# PROC054D_System_Power.net
KiCad netlist of a schematic drawn in Altium Designer
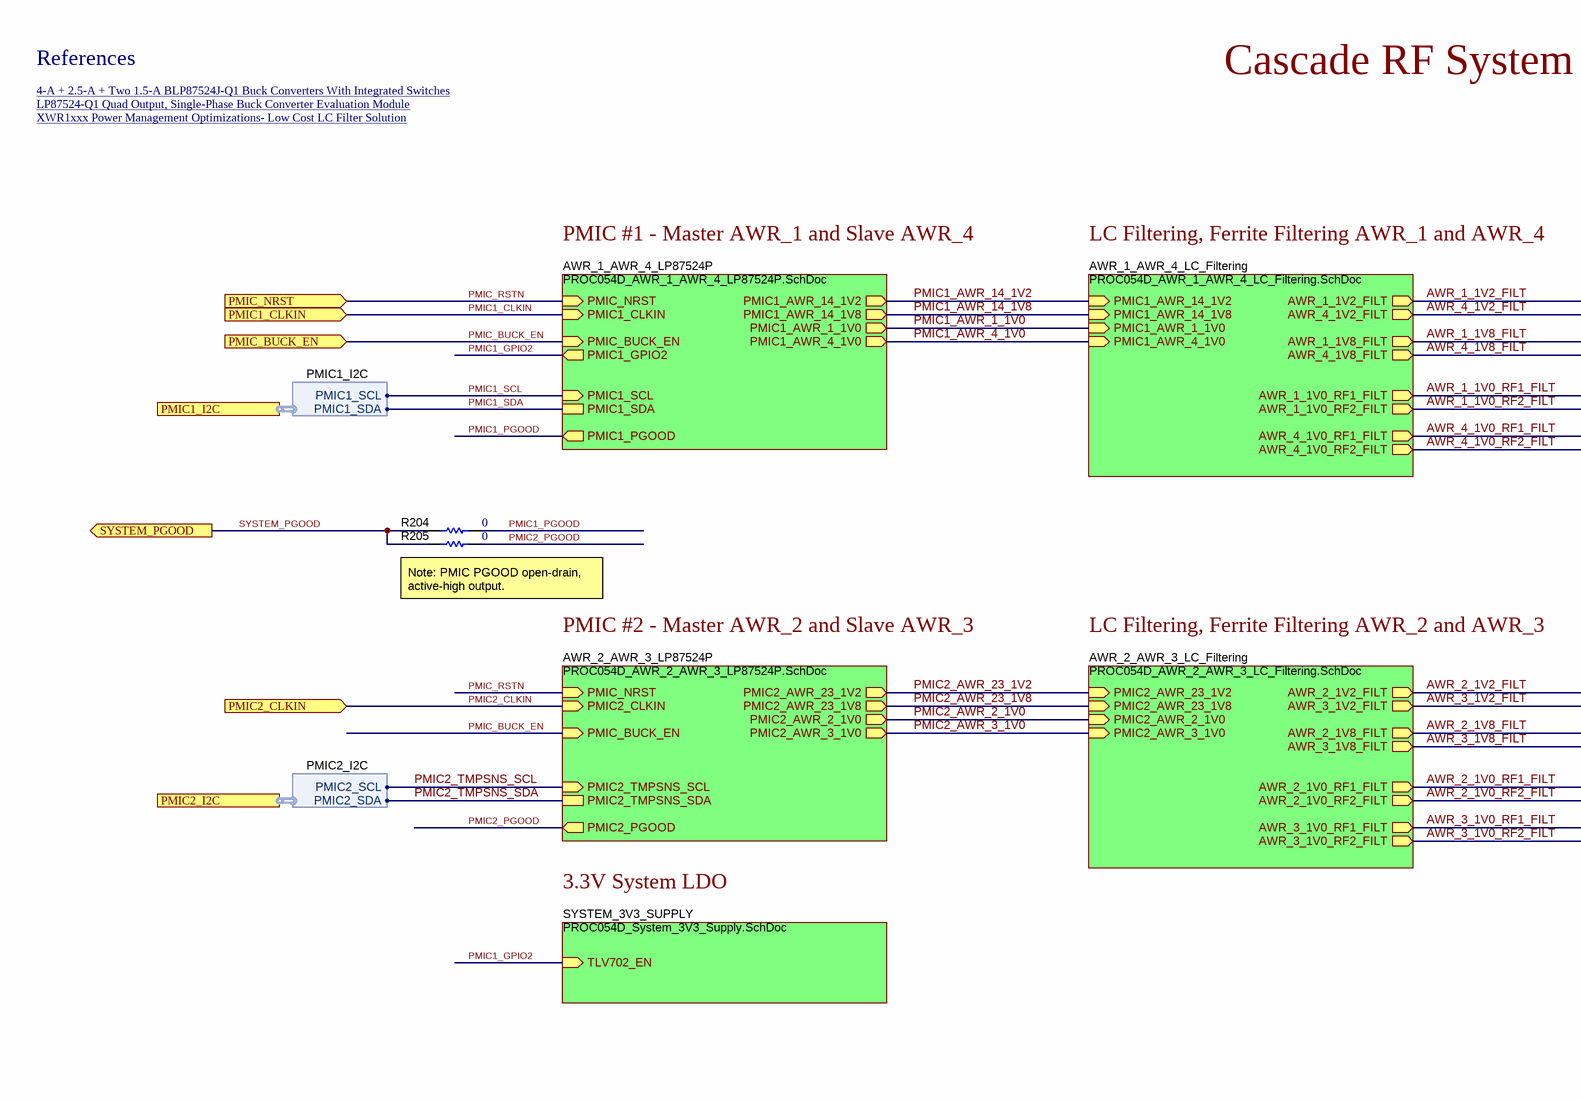
[diagram p0: PROC054D_System_Power.SchDoc, top left]
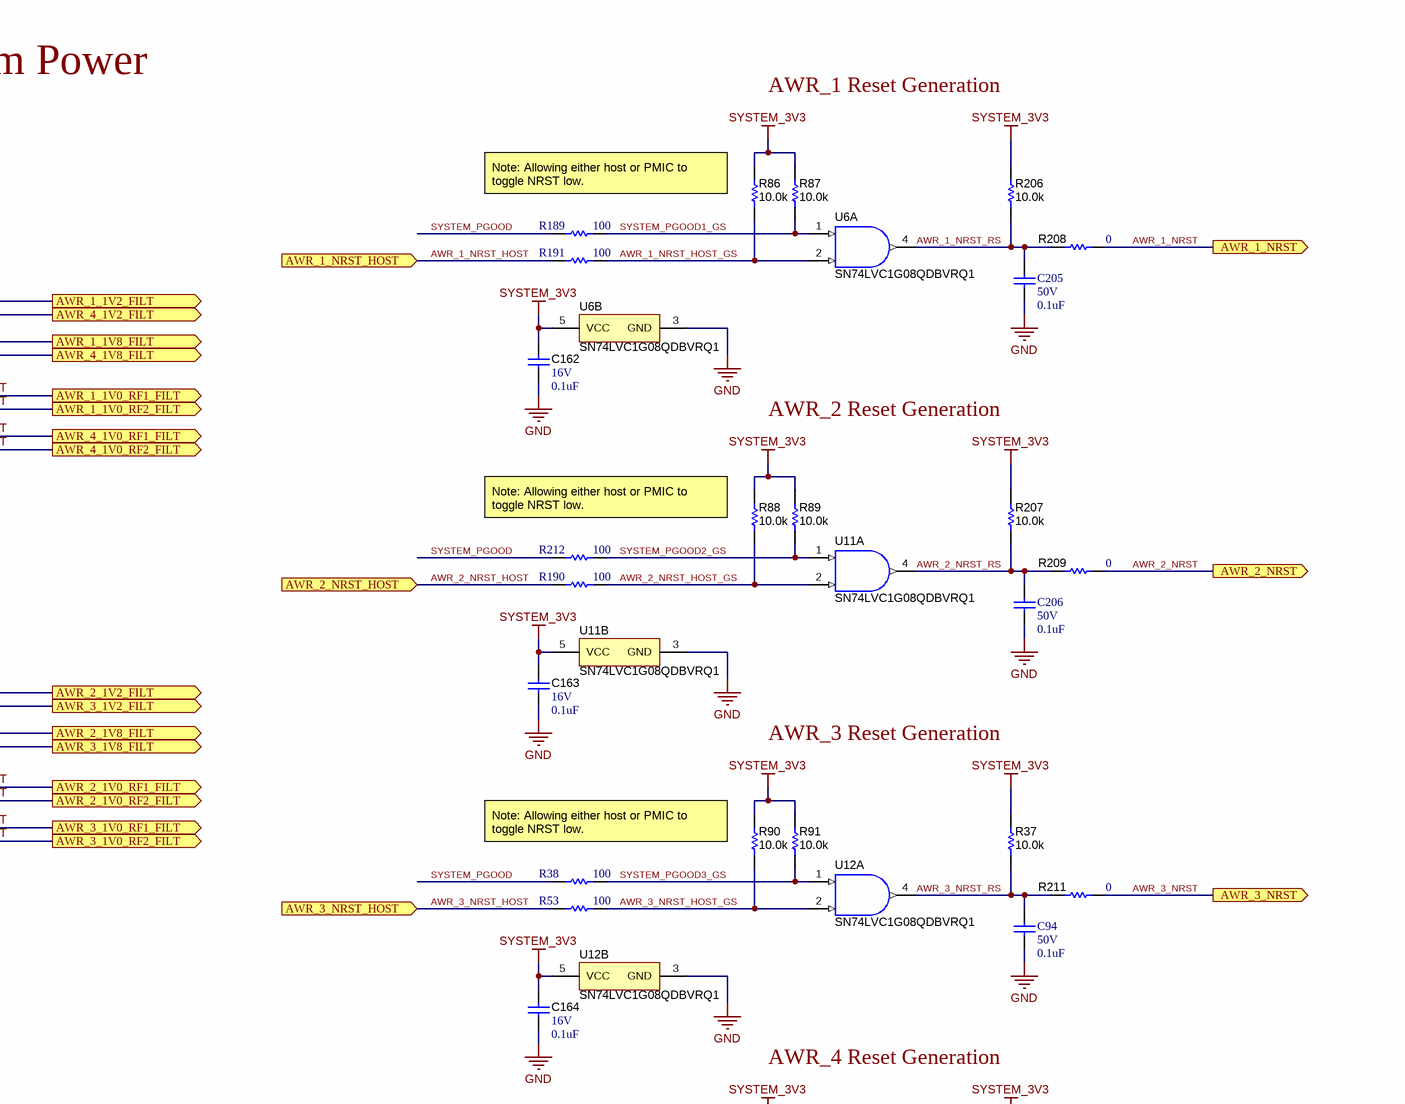
[diagram p1: PROC054D_System_Power.SchDoc, top right]
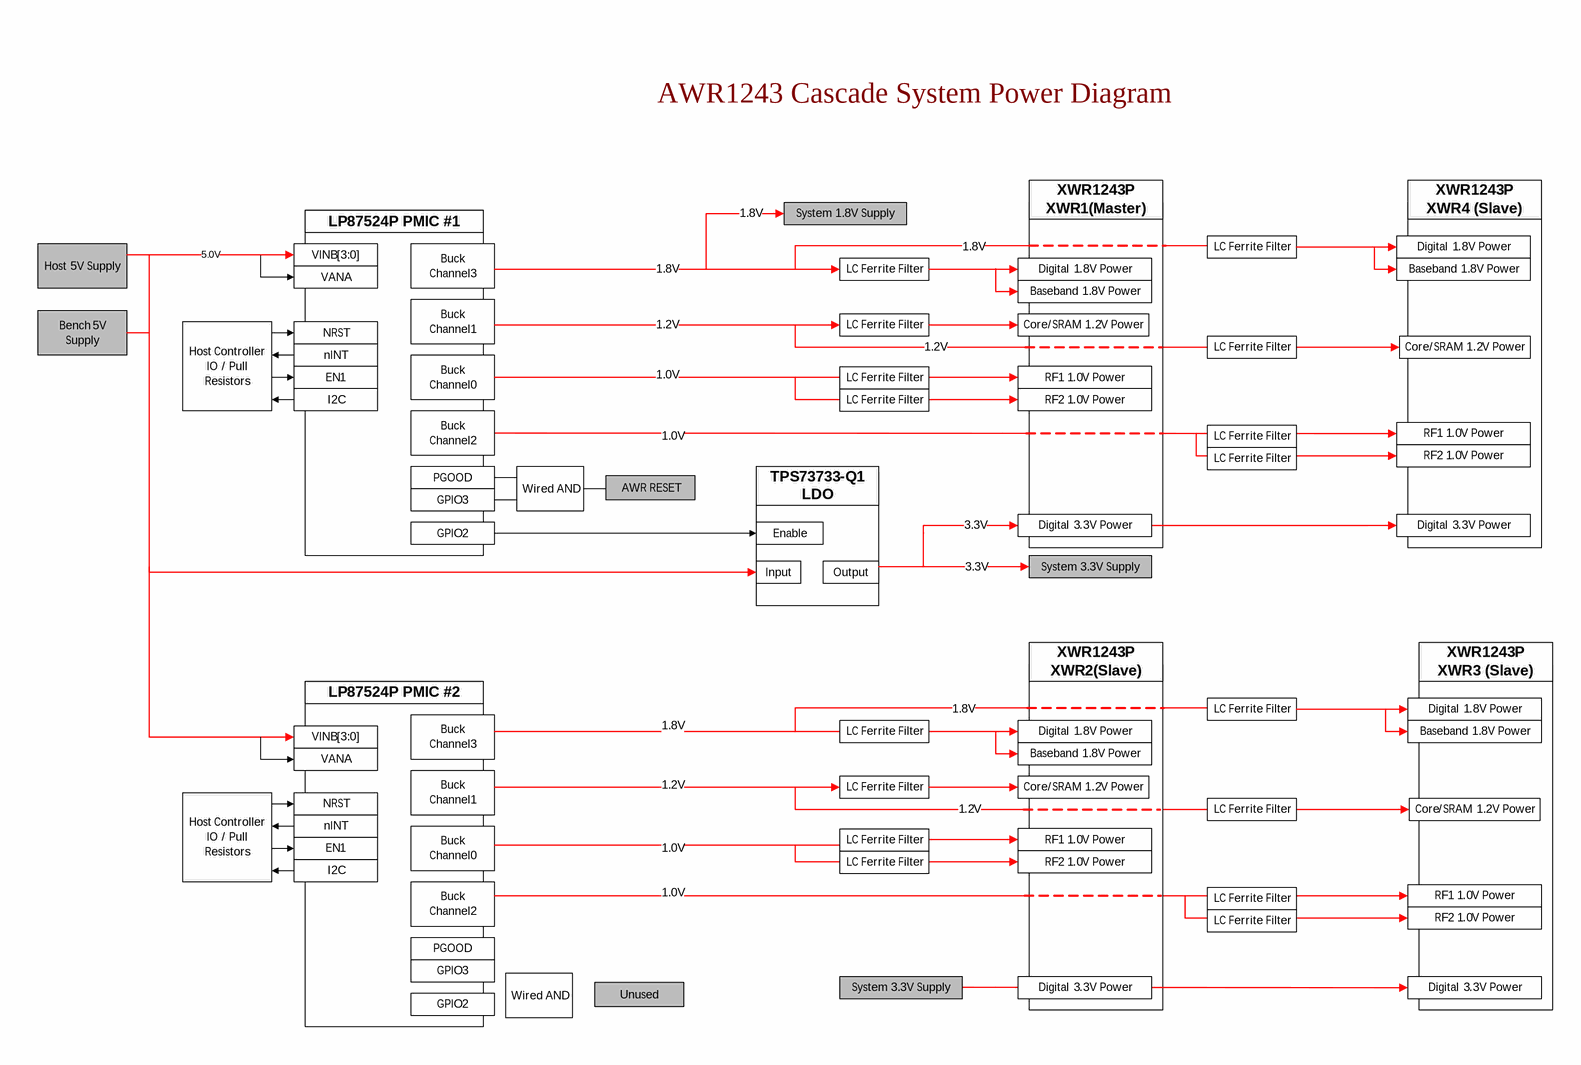
[diagram p2: PROC054D_System_Power.SchDoc, bottom left]
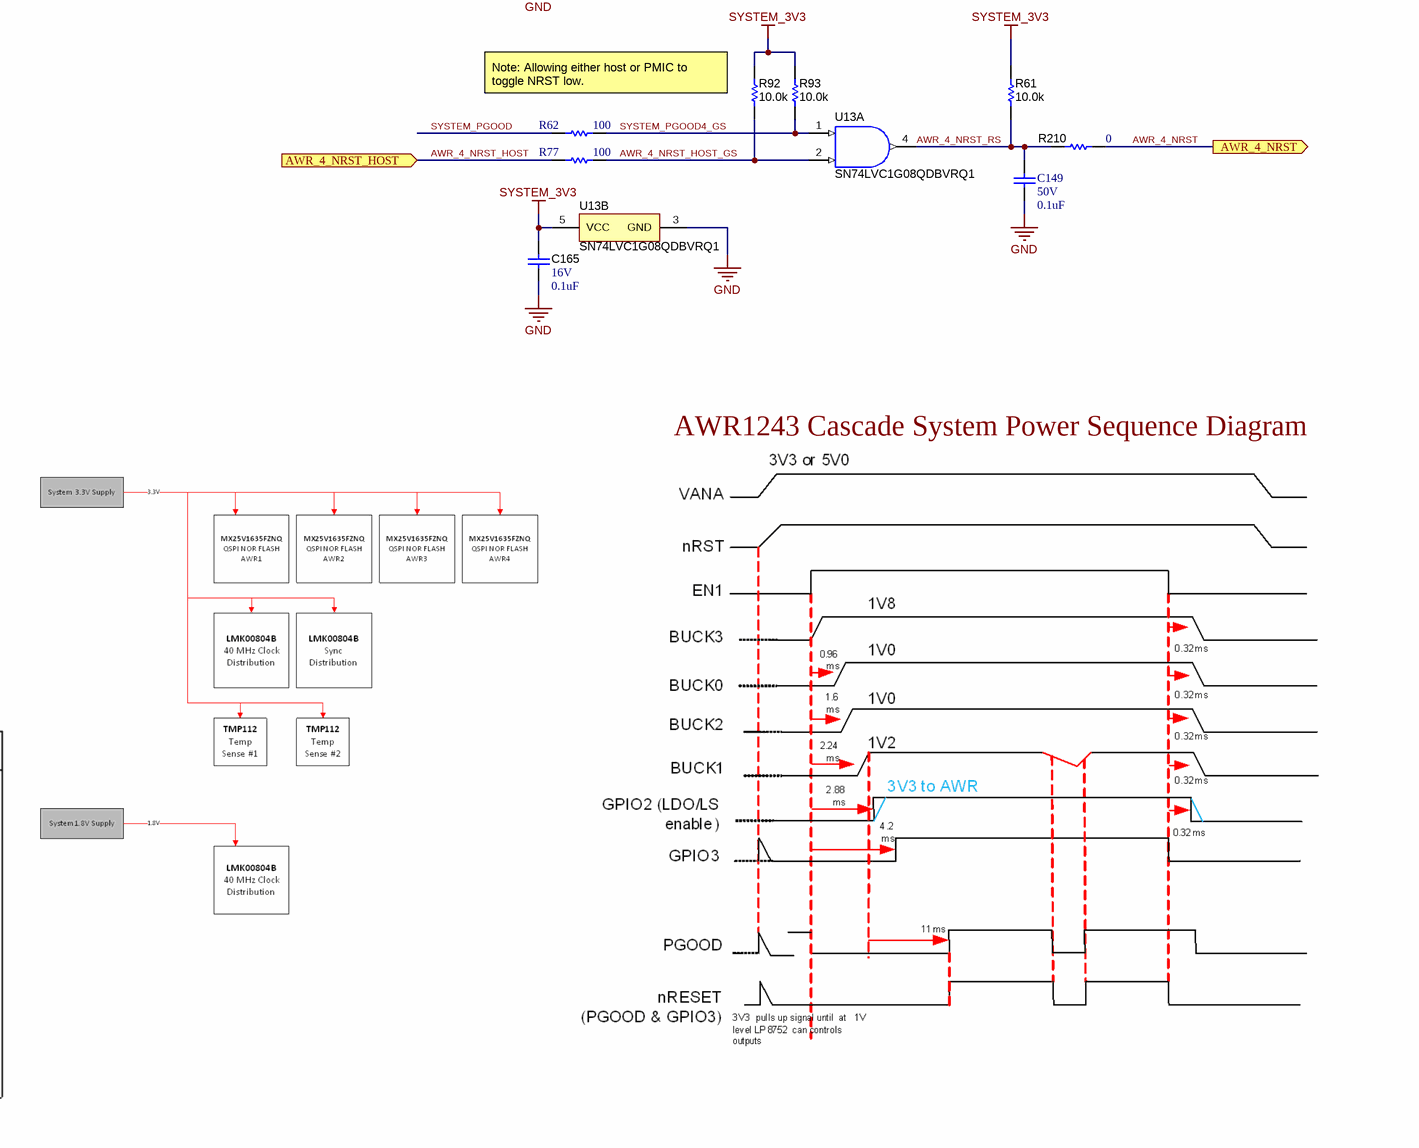
[diagram p3: PROC054D_System_Power.SchDoc, bottom right]

(export (version "E")
  (design (tool "Eeschema 10.0.6"))
  (components
    (comp (ref "C94")
      (value "CGA2B3X7R1H104K050BB")
      (footprint "0402")
      (description "CAP, CERM, 0.1 uF, 50 V, +/- 10%, X7R, AEC-Q200 Grade 1, 0402")
      (fields
        (field (name "MANUFACTURER") "TDK")
        (field (name "VDC_V") "50V")
        (field (name "VALUEDISPLAYED") "0.1uF")
        (field (name "PUBLISHER") "Texas Instruments")
      )
      (libsource (lib "Altium Vault - TI") (part "Capacitor"))
    )
    (comp (ref "C149")
      (value "CGA2B3X7R1H104K050BB")
      (footprint "0402")
      (description "CAP, CERM, 0.1 uF, 50 V, +/- 10%, X7R, AEC-Q200 Grade 1, 0402")
      (fields
        (field (name "MANUFACTURER") "TDK")
        (field (name "VDC_V") "50V")
        (field (name "VALUEDISPLAYED") "0.1uF")
        (field (name "PUBLISHER") "Texas Instruments")
      )
      (libsource (lib "Altium Vault - TI") (part "Capacitor"))
    )
    (comp (ref "C162")
      (value "GCM155R71C104KA55D")
      (footprint "0402")
      (description "CAP, CERM, 0.1 uF, 16 V, +/- 10%, X7R, 0402")
      (fields
        (field (name "MANUFACTURER") "MuRata")
        (field (name "VDC_V") "16V")
        (field (name "VALUEDISPLAYED") "0.1uF")
        (field (name "PUBLISHER") "Texas Instruments")
      )
      (libsource (lib "Altium Vault - TI") (part "Capacitor"))
    )
    (comp (ref "C163")
      (value "GCM155R71C104KA55D")
      (footprint "0402")
      (description "CAP, CERM, 0.1 uF, 16 V, +/- 10%, X7R, 0402")
      (fields
        (field (name "MANUFACTURER") "MuRata")
        (field (name "VDC_V") "16V")
        (field (name "VALUEDISPLAYED") "0.1uF")
        (field (name "PUBLISHER") "Texas Instruments")
      )
      (libsource (lib "Altium Vault - TI") (part "Capacitor"))
    )
    (comp (ref "C164")
      (value "GCM155R71C104KA55D")
      (footprint "0402")
      (description "CAP, CERM, 0.1 uF, 16 V, +/- 10%, X7R, 0402")
      (fields
        (field (name "MANUFACTURER") "MuRata")
        (field (name "VDC_V") "16V")
        (field (name "VALUEDISPLAYED") "0.1uF")
        (field (name "PUBLISHER") "Texas Instruments")
      )
      (libsource (lib "Altium Vault - TI") (part "Capacitor"))
    )
    (comp (ref "C165")
      (value "GCM155R71C104KA55D")
      (footprint "0402")
      (description "CAP, CERM, 0.1 uF, 16 V, +/- 10%, X7R, 0402")
      (fields
        (field (name "MANUFACTURER") "MuRata")
        (field (name "VDC_V") "16V")
        (field (name "VALUEDISPLAYED") "0.1uF")
        (field (name "PUBLISHER") "Texas Instruments")
      )
      (libsource (lib "Altium Vault - TI") (part "Capacitor"))
    )
    (comp (ref "C205")
      (value "CGA2B3X7R1H104K050BB")
      (footprint "0402")
      (description "CAP, CERM, 0.1 uF, 50 V, +/- 10%, X7R, AEC-Q200 Grade 1, 0402")
      (fields
        (field (name "MANUFACTURER") "TDK")
        (field (name "VDC_V") "50V")
        (field (name "VALUEDISPLAYED") "0.1uF")
        (field (name "PUBLISHER") "Texas Instruments")
      )
      (libsource (lib "Altium Vault - TI") (part "Capacitor"))
    )
    (comp (ref "C206")
      (value "CGA2B3X7R1H104K050BB")
      (footprint "0402")
      (description "CAP, CERM, 0.1 uF, 50 V, +/- 10%, X7R, AEC-Q200 Grade 1, 0402")
      (fields
        (field (name "MANUFACTURER") "TDK")
        (field (name "VDC_V") "50V")
        (field (name "VALUEDISPLAYED") "0.1uF")
        (field (name "PUBLISHER") "Texas Instruments")
      )
      (libsource (lib "Altium Vault - TI") (part "Capacitor"))
    )
    (comp (ref "R37")
      (value "CRCW040210K0FKED")
      (footprint "0402")
      (description "RES, 10.0 k, 1%, 0.063 W, AEC-Q200 Grade 0, 0402")
      (fields (field (name "MANUFACTURER") "Vishay-Dale") (field (name "VALUEDISPLAYED") "10.0k"))
      (libsource (lib "Altium Vault - TI") (part "Resistor"))
    )
    (comp (ref "R38")
      (value "MCS0402MD1000BE100")
      (footprint "0402")
      (description "RES, 100, 0.1%, 0.1 W, AEC-Q200 Grade 0, 0402")
      (fields
        (field (name "MANUFACTURER") "Vishay/Beyschlag")
        (field (name "VALUEDISPLAYED") "100")
        (field (name "PUBLISHER") "Texas Instruments")
      )
      (libsource (lib "Altium Vault - TI") (part "Resistor"))
    )
    (comp (ref "R53")
      (value "MCS0402MD1000BE100")
      (footprint "0402")
      (description "RES, 100, 0.1%, 0.1 W, AEC-Q200 Grade 0, 0402")
      (fields
        (field (name "MANUFACTURER") "Vishay/Beyschlag")
        (field (name "VALUEDISPLAYED") "100")
        (field (name "PUBLISHER") "Texas Instruments")
      )
      (libsource (lib "Altium Vault - TI") (part "Resistor"))
    )
    (comp (ref "R61")
      (value "CRCW040210K0FKED")
      (footprint "0402")
      (description "RES, 10.0 k, 1%, 0.063 W, AEC-Q200 Grade 0, 0402")
      (fields (field (name "MANUFACTURER") "Vishay-Dale") (field (name "VALUEDISPLAYED") "10.0k"))
      (libsource (lib "Altium Vault - TI") (part "Resistor"))
    )
    (comp (ref "R62")
      (value "MCS0402MD1000BE100")
      (footprint "0402")
      (description "RES, 100, 0.1%, 0.1 W, AEC-Q200 Grade 0, 0402")
      (fields
        (field (name "MANUFACTURER") "Vishay/Beyschlag")
        (field (name "VALUEDISPLAYED") "100")
        (field (name "PUBLISHER") "Texas Instruments")
      )
      (libsource (lib "Altium Vault - TI") (part "Resistor"))
    )
    (comp (ref "R77")
      (value "MCS0402MD1000BE100")
      (footprint "0402")
      (description "RES, 100, 0.1%, 0.1 W, AEC-Q200 Grade 0, 0402")
      (fields
        (field (name "MANUFACTURER") "Vishay/Beyschlag")
        (field (name "VALUEDISPLAYED") "100")
        (field (name "PUBLISHER") "Texas Instruments")
      )
      (libsource (lib "Altium Vault - TI") (part "Resistor"))
    )
    (comp (ref "R86")
      (value "CRCW040210K0FKED")
      (footprint "0402")
      (description "RES, 10.0 k, 1%, 0.063 W, AEC-Q200 Grade 0, 0402")
      (fields (field (name "MANUFACTURER") "Vishay-Dale") (field (name "VALUEDISPLAYED") "10.0k"))
      (libsource (lib "Altium Vault - TI") (part "Resistor"))
    )
    (comp (ref "R87")
      (value "CRCW040210K0FKED")
      (footprint "0402")
      (description "RES, 10.0 k, 1%, 0.063 W, AEC-Q200 Grade 0, 0402")
      (fields (field (name "MANUFACTURER") "Vishay-Dale") (field (name "VALUEDISPLAYED") "10.0k"))
      (libsource (lib "Altium Vault - TI") (part "Resistor"))
    )
    (comp (ref "R88")
      (value "CRCW040210K0FKED")
      (footprint "0402")
      (description "RES, 10.0 k, 1%, 0.063 W, AEC-Q200 Grade 0, 0402")
      (fields (field (name "MANUFACTURER") "Vishay-Dale") (field (name "VALUEDISPLAYED") "10.0k"))
      (libsource (lib "Altium Vault - TI") (part "Resistor"))
    )
    (comp (ref "R89")
      (value "CRCW040210K0FKED")
      (footprint "0402")
      (description "RES, 10.0 k, 1%, 0.063 W, AEC-Q200 Grade 0, 0402")
      (fields (field (name "MANUFACTURER") "Vishay-Dale") (field (name "VALUEDISPLAYED") "10.0k"))
      (libsource (lib "Altium Vault - TI") (part "Resistor"))
    )
    (comp (ref "R90")
      (value "CRCW040210K0FKED")
      (footprint "0402")
      (description "RES, 10.0 k, 1%, 0.063 W, AEC-Q200 Grade 0, 0402")
      (fields (field (name "MANUFACTURER") "Vishay-Dale") (field (name "VALUEDISPLAYED") "10.0k"))
      (libsource (lib "Altium Vault - TI") (part "Resistor"))
    )
    (comp (ref "R91")
      (value "CRCW040210K0FKED")
      (footprint "0402")
      (description "RES, 10.0 k, 1%, 0.063 W, AEC-Q200 Grade 0, 0402")
      (fields (field (name "MANUFACTURER") "Vishay-Dale") (field (name "VALUEDISPLAYED") "10.0k"))
      (libsource (lib "Altium Vault - TI") (part "Resistor"))
    )
    (comp (ref "R92")
      (value "CRCW040210K0FKED")
      (footprint "0402")
      (description "RES, 10.0 k, 1%, 0.063 W, AEC-Q200 Grade 0, 0402")
      (fields (field (name "MANUFACTURER") "Vishay-Dale") (field (name "VALUEDISPLAYED") "10.0k"))
      (libsource (lib "Altium Vault - TI") (part "Resistor"))
    )
    (comp (ref "R93")
      (value "CRCW040210K0FKED")
      (footprint "0402")
      (description "RES, 10.0 k, 1%, 0.063 W, AEC-Q200 Grade 0, 0402")
      (fields (field (name "MANUFACTURER") "Vishay-Dale") (field (name "VALUEDISPLAYED") "10.0k"))
      (libsource (lib "Altium Vault - TI") (part "Resistor"))
    )
    (comp (ref "R189")
      (value "MCS0402MD1000BE100")
      (footprint "0402")
      (description "RES, 100, 0.1%, 0.1 W, AEC-Q200 Grade 0, 0402")
      (fields
        (field (name "MANUFACTURER") "Vishay/Beyschlag")
        (field (name "VALUEDISPLAYED") "100")
        (field (name "PUBLISHER") "Texas Instruments")
      )
      (libsource (lib "Altium Vault - TI") (part "Resistor"))
    )
    (comp (ref "R190")
      (value "MCS0402MD1000BE100")
      (footprint "0402")
      (description "RES, 100, 0.1%, 0.1 W, AEC-Q200 Grade 0, 0402")
      (fields
        (field (name "MANUFACTURER") "Vishay/Beyschlag")
        (field (name "VALUEDISPLAYED") "100")
        (field (name "PUBLISHER") "Texas Instruments")
      )
      (libsource (lib "Altium Vault - TI") (part "Resistor"))
    )
    (comp (ref "R191")
      (value "MCS0402MD1000BE100")
      (footprint "0402")
      (description "RES, 100, 0.1%, 0.1 W, AEC-Q200 Grade 0, 0402")
      (fields
        (field (name "MANUFACTURER") "Vishay/Beyschlag")
        (field (name "VALUEDISPLAYED") "100")
        (field (name "PUBLISHER") "Texas Instruments")
      )
      (libsource (lib "Altium Vault - TI") (part "Resistor"))
    )
    (comp (ref "R204")
      (value "ERJ-2GE0R00X")
      (footprint "0402")
      (description "RES, 0, 5%, 0.1 W, AEC-Q200 Grade 0, 0402")
      (fields (field (name "MANUFACTURER") "Panasonic") (field (name "VALUEDISPLAYED") "0"))
      (libsource (lib "Altium Vault - TI") (part "Resistor"))
    )
    (comp (ref "R205")
      (value "ERJ-2GE0R00X")
      (footprint "0402")
      (description "RES, 0, 5%, 0.1 W, AEC-Q200 Grade 0, 0402")
      (fields (field (name "MANUFACTURER") "Panasonic") (field (name "VALUEDISPLAYED") "0"))
      (libsource (lib "Altium Vault - TI") (part "Resistor"))
    )
    (comp (ref "R206")
      (value "CRCW040210K0FKED")
      (footprint "0402")
      (description "RES, 10.0 k, 1%, 0.063 W, AEC-Q200 Grade 0, 0402")
      (fields (field (name "MANUFACTURER") "Vishay-Dale") (field (name "VALUEDISPLAYED") "10.0k"))
      (libsource (lib "Altium Vault - TI") (part "Resistor"))
    )
    (comp (ref "R207")
      (value "CRCW040210K0FKED")
      (footprint "0402")
      (description "RES, 10.0 k, 1%, 0.063 W, AEC-Q200 Grade 0, 0402")
      (fields (field (name "MANUFACTURER") "Vishay-Dale") (field (name "VALUEDISPLAYED") "10.0k"))
      (libsource (lib "Altium Vault - TI") (part "Resistor"))
    )
    (comp (ref "R208")
      (value "ERJ-2GE0R00X")
      (footprint "0402")
      (description "RES, 0, 5%, 0.1 W, AEC-Q200 Grade 0, 0402")
      (fields (field (name "MANUFACTURER") "Panasonic") (field (name "VALUEDISPLAYED") "0"))
      (libsource (lib "Altium Vault - TI") (part "Resistor"))
    )
    (comp (ref "R209")
      (value "ERJ-2GE0R00X")
      (footprint "0402")
      (description "RES, 0, 5%, 0.1 W, AEC-Q200 Grade 0, 0402")
      (fields (field (name "MANUFACTURER") "Panasonic") (field (name "VALUEDISPLAYED") "0"))
      (libsource (lib "Altium Vault - TI") (part "Resistor"))
    )
    (comp (ref "R210")
      (value "ERJ-2GE0R00X")
      (footprint "0402")
      (description "RES, 0, 5%, 0.1 W, AEC-Q200 Grade 0, 0402")
      (fields (field (name "MANUFACTURER") "Panasonic") (field (name "VALUEDISPLAYED") "0"))
      (libsource (lib "Altium Vault - TI") (part "Resistor"))
    )
    (comp (ref "R211")
      (value "ERJ-2GE0R00X")
      (footprint "0402")
      (description "RES, 0, 5%, 0.1 W, AEC-Q200 Grade 0, 0402")
      (fields (field (name "MANUFACTURER") "Panasonic") (field (name "VALUEDISPLAYED") "0"))
      (libsource (lib "Altium Vault - TI") (part "Resistor"))
    )
    (comp (ref "R212")
      (value "MCS0402MD1000BE100")
      (footprint "0402")
      (description "RES, 100, 0.1%, 0.1 W, AEC-Q200 Grade 0, 0402")
      (fields
        (field (name "MANUFACTURER") "Vishay/Beyschlag")
        (field (name "VALUEDISPLAYED") "100")
        (field (name "PUBLISHER") "Texas Instruments")
      )
      (libsource (lib "Altium Vault - TI") (part "Resistor"))
    )
    (comp (ref "U6")
      (value "SN74LVC1G08QDBVRQ1")
      (footprint "DBV0005A_N")
      (description "Automotive Catalog Single 2-Input Positive-AND Gate, DBV0005A, LARGE T&R")
      (fields
        (field (name "MANUFACTURER") "Texas Instruments")
        (field (name "GENERIC PART NUMBER") "SN74LVC1G08-Q1")
        (field (name "PARTNUMBER") "SN74LVC1G08QDBVRQ1")
      )
      (libsource (lib "Altium Vault - TI") (part "TI-SN74XXX1X08-5"))
    )
    (comp (ref "U11")
      (value "SN74LVC1G08QDBVRQ1")
      (footprint "DBV0005A_N")
      (description "Automotive Catalog Single 2-Input Positive-AND Gate, DBV0005A, LARGE T&R")
      (fields
        (field (name "MANUFACTURER") "Texas Instruments")
        (field (name "GENERIC PART NUMBER") "SN74LVC1G08-Q1")
        (field (name "PARTNUMBER") "SN74LVC1G08QDBVRQ1")
      )
      (libsource (lib "Altium Vault - TI") (part "TI-SN74XXX1X08-5"))
    )
    (comp (ref "U12")
      (value "SN74LVC1G08QDBVRQ1")
      (footprint "DBV0005A_N")
      (description "Automotive Catalog Single 2-Input Positive-AND Gate, DBV0005A, LARGE T&R")
      (fields
        (field (name "MANUFACTURER") "Texas Instruments")
        (field (name "GENERIC PART NUMBER") "SN74LVC1G08-Q1")
        (field (name "PARTNUMBER") "SN74LVC1G08QDBVRQ1")
      )
      (libsource (lib "Altium Vault - TI") (part "TI-SN74XXX1X08-5"))
    )
    (comp (ref "U13")
      (value "SN74LVC1G08QDBVRQ1")
      (footprint "DBV0005A_N")
      (description "Automotive Catalog Single 2-Input Positive-AND Gate, DBV0005A, LARGE T&R")
      (fields
        (field (name "MANUFACTURER") "Texas Instruments")
        (field (name "GENERIC PART NUMBER") "SN74LVC1G08-Q1")
        (field (name "PARTNUMBER") "SN74LVC1G08QDBVRQ1")
      )
      (libsource (lib "Altium Vault - TI") (part "TI-SN74XXX1X08-5"))
    )
  )
  (nets
    (net (code "7") (name "/AWR_1_NRST") (class "Default")
      (node (ref "R208") (pin "2") (pinfunction "2_2") (pintype "passive"))
    )
    (net (code "8") (name "/AWR_1_NRST_HOST") (class "Default")
      (node (ref "R191") (pin "1") (pinfunction "1_1") (pintype "passive"))
    )
    (net (code "9") (name "/AWR_1_NRST_HOST_GS") (class "Default")
      (node (ref "R191") (pin "2") (pinfunction "2_2") (pintype "passive"))
      (node (ref "R86") (pin "1") (pinfunction "1_1") (pintype "passive"))
      (node (ref "U6") (pin "2") (pinfunction "B_2") (pintype "input"))
    )
    (net (code "10") (name "/AWR_1_NRST_RS") (class "Default")
      (node (ref "C205") (pin "1") (pinfunction "1_1") (pintype "passive"))
      (node (ref "R206") (pin "1") (pinfunction "1_1") (pintype "passive"))
      (node (ref "R208") (pin "1") (pinfunction "1_1") (pintype "passive"))
      (node (ref "U6") (pin "4") (pinfunction "Y_4") (pintype "output"))
    )
    (net (code "15") (name "/AWR_2_NRST") (class "Default")
      (node (ref "R209") (pin "2") (pinfunction "2_2") (pintype "passive"))
    )
    (net (code "16") (name "/AWR_2_NRST_HOST") (class "Default")
      (node (ref "R190") (pin "1") (pinfunction "1_1") (pintype "passive"))
    )
    (net (code "17") (name "/AWR_2_NRST_HOST_GS") (class "Default")
      (node (ref "R190") (pin "2") (pinfunction "2_2") (pintype "passive"))
      (node (ref "R88") (pin "1") (pinfunction "1_1") (pintype "passive"))
      (node (ref "U11") (pin "2") (pinfunction "B_2") (pintype "input"))
    )
    (net (code "18") (name "/AWR_2_NRST_RS") (class "Default")
      (node (ref "C206") (pin "1") (pinfunction "1_1") (pintype "passive"))
      (node (ref "R207") (pin "1") (pinfunction "1_1") (pintype "passive"))
      (node (ref "R209") (pin "1") (pinfunction "1_1") (pintype "passive"))
      (node (ref "U11") (pin "4") (pinfunction "Y_4") (pintype "output"))
    )
    (net (code "23") (name "/AWR_3_NRST") (class "Default")
      (node (ref "R211") (pin "2") (pinfunction "2_2") (pintype "passive"))
    )
    (net (code "24") (name "/AWR_3_NRST_HOST") (class "Default")
      (node (ref "R53") (pin "1") (pinfunction "1_1") (pintype "passive"))
    )
    (net (code "25") (name "/AWR_3_NRST_HOST_GS") (class "Default")
      (node (ref "R53") (pin "2") (pinfunction "2_2") (pintype "passive"))
      (node (ref "R90") (pin "1") (pinfunction "1_1") (pintype "passive"))
      (node (ref "U12") (pin "2") (pinfunction "B_2") (pintype "input"))
    )
    (net (code "26") (name "/AWR_3_NRST_RS") (class "Default")
      (node (ref "C94") (pin "1") (pinfunction "1_1") (pintype "passive"))
      (node (ref "R211") (pin "1") (pinfunction "1_1") (pintype "passive"))
      (node (ref "R37") (pin "1") (pinfunction "1_1") (pintype "passive"))
      (node (ref "U12") (pin "4") (pinfunction "Y_4") (pintype "output"))
    )
    (net (code "31") (name "/AWR_4_NRST") (class "Default")
      (node (ref "R210") (pin "2") (pinfunction "2_2") (pintype "passive"))
    )
    (net (code "32") (name "/AWR_4_NRST_HOST") (class "Default")
      (node (ref "R77") (pin "1") (pinfunction "1_1") (pintype "passive"))
    )
    (net (code "33") (name "/AWR_4_NRST_HOST_GS") (class "Default")
      (node (ref "R77") (pin "2") (pinfunction "2_2") (pintype "passive"))
      (node (ref "R92") (pin "1") (pinfunction "1_1") (pintype "passive"))
      (node (ref "U13") (pin "2") (pinfunction "B_2") (pintype "input"))
    )
    (net (code "34") (name "/AWR_4_NRST_RS") (class "Default")
      (node (ref "C149") (pin "1") (pinfunction "1_1") (pintype "passive"))
      (node (ref "R210") (pin "1") (pinfunction "1_1") (pintype "passive"))
      (node (ref "R61") (pin "1") (pinfunction "1_1") (pintype "passive"))
      (node (ref "U13") (pin "4") (pinfunction "Y_4") (pintype "output"))
    )
    (net (code "41") (name "/PMIC1_PGOOD") (class "Default")
      (node (ref "R204") (pin "2") (pinfunction "2_2") (pintype "passive"))
    )
    (net (code "49") (name "/PMIC2_PGOOD") (class "Default")
      (node (ref "R205") (pin "2") (pinfunction "2_2") (pintype "passive"))
    )
    (net (code "54") (name "/SYSTEM_PGOOD") (class "Default")
      (node (ref "R189") (pin "1") (pinfunction "1_1") (pintype "passive"))
      (node (ref "R204") (pin "1") (pinfunction "1_1") (pintype "passive"))
      (node (ref "R205") (pin "1") (pinfunction "1_1") (pintype "passive"))
      (node (ref "R212") (pin "1") (pinfunction "1_1") (pintype "passive"))
      (node (ref "R38") (pin "1") (pinfunction "1_1") (pintype "passive"))
      (node (ref "R62") (pin "1") (pinfunction "1_1") (pintype "passive"))
    )
    (net (code "55") (name "/SYSTEM_PGOOD1_GS") (class "Default")
      (node (ref "R189") (pin "2") (pinfunction "2_2") (pintype "passive"))
      (node (ref "R87") (pin "1") (pinfunction "1_1") (pintype "passive"))
      (node (ref "U6") (pin "1") (pinfunction "A_1") (pintype "input"))
    )
    (net (code "56") (name "/SYSTEM_PGOOD2_GS") (class "Default")
      (node (ref "R212") (pin "2") (pinfunction "2_2") (pintype "passive"))
      (node (ref "R89") (pin "1") (pinfunction "1_1") (pintype "passive"))
      (node (ref "U11") (pin "1") (pinfunction "A_1") (pintype "input"))
    )
    (net (code "57") (name "/SYSTEM_PGOOD3_GS") (class "Default")
      (node (ref "R38") (pin "2") (pinfunction "2_2") (pintype "passive"))
      (node (ref "R91") (pin "1") (pinfunction "1_1") (pintype "passive"))
      (node (ref "U12") (pin "1") (pinfunction "A_1") (pintype "input"))
    )
    (net (code "58") (name "/SYSTEM_PGOOD4_GS") (class "Default")
      (node (ref "R62") (pin "2") (pinfunction "2_2") (pintype "passive"))
      (node (ref "R93") (pin "1") (pinfunction "1_1") (pintype "passive"))
      (node (ref "U13") (pin "1") (pinfunction "A_1") (pintype "input"))
    )
    (net (code "61") (name "GND") (class "Default")
      (node (ref "C149") (pin "2") (pinfunction "2_2") (pintype "passive"))
      (node (ref "C162") (pin "2") (pinfunction "2_2") (pintype "passive"))
      (node (ref "C163") (pin "2") (pinfunction "2_2") (pintype "passive"))
      (node (ref "C164") (pin "2") (pinfunction "2_2") (pintype "passive"))
      (node (ref "C165") (pin "2") (pinfunction "2_2") (pintype "passive"))
      (node (ref "C205") (pin "2") (pinfunction "2_2") (pintype "passive"))
      (node (ref "C206") (pin "2") (pinfunction "2_2") (pintype "passive"))
      (node (ref "C94") (pin "2") (pinfunction "2_2") (pintype "passive"))
      (node (ref "U11") (pin "3") (pinfunction "GND_3") (pintype "power_in"))
      (node (ref "U12") (pin "3") (pinfunction "GND_3") (pintype "power_in"))
      (node (ref "U13") (pin "3") (pinfunction "GND_3") (pintype "power_in"))
      (node (ref "U6") (pin "3") (pinfunction "GND_3") (pintype "power_in"))
    )
    (net (code "62") (name "SYSTEM_3V3") (class "Default")
      (node (ref "C162") (pin "1") (pinfunction "1_1") (pintype "passive"))
      (node (ref "C163") (pin "1") (pinfunction "1_1") (pintype "passive"))
      (node (ref "C164") (pin "1") (pinfunction "1_1") (pintype "passive"))
      (node (ref "C165") (pin "1") (pinfunction "1_1") (pintype "passive"))
      (node (ref "R206") (pin "2") (pinfunction "2_2") (pintype "passive"))
      (node (ref "R207") (pin "2") (pinfunction "2_2") (pintype "passive"))
      (node (ref "R37") (pin "2") (pinfunction "2_2") (pintype "passive"))
      (node (ref "R61") (pin "2") (pinfunction "2_2") (pintype "passive"))
      (node (ref "R86") (pin "2") (pinfunction "2_2") (pintype "passive"))
      (node (ref "R87") (pin "2") (pinfunction "2_2") (pintype "passive"))
      (node (ref "R88") (pin "2") (pinfunction "2_2") (pintype "passive"))
      (node (ref "R89") (pin "2") (pinfunction "2_2") (pintype "passive"))
      (node (ref "R90") (pin "2") (pinfunction "2_2") (pintype "passive"))
      (node (ref "R91") (pin "2") (pinfunction "2_2") (pintype "passive"))
      (node (ref "R92") (pin "2") (pinfunction "2_2") (pintype "passive"))
      (node (ref "R93") (pin "2") (pinfunction "2_2") (pintype "passive"))
      (node (ref "U11") (pin "5") (pinfunction "VCC_5") (pintype "power_in"))
      (node (ref "U12") (pin "5") (pinfunction "VCC_5") (pintype "power_in"))
      (node (ref "U13") (pin "5") (pinfunction "VCC_5") (pintype "power_in"))
      (node (ref "U6") (pin "5") (pinfunction "VCC_5") (pintype "power_in"))
    )
  )
)
